# WATCHDOG.net
KiCad netlist of a schematic drawn in Altium Designer
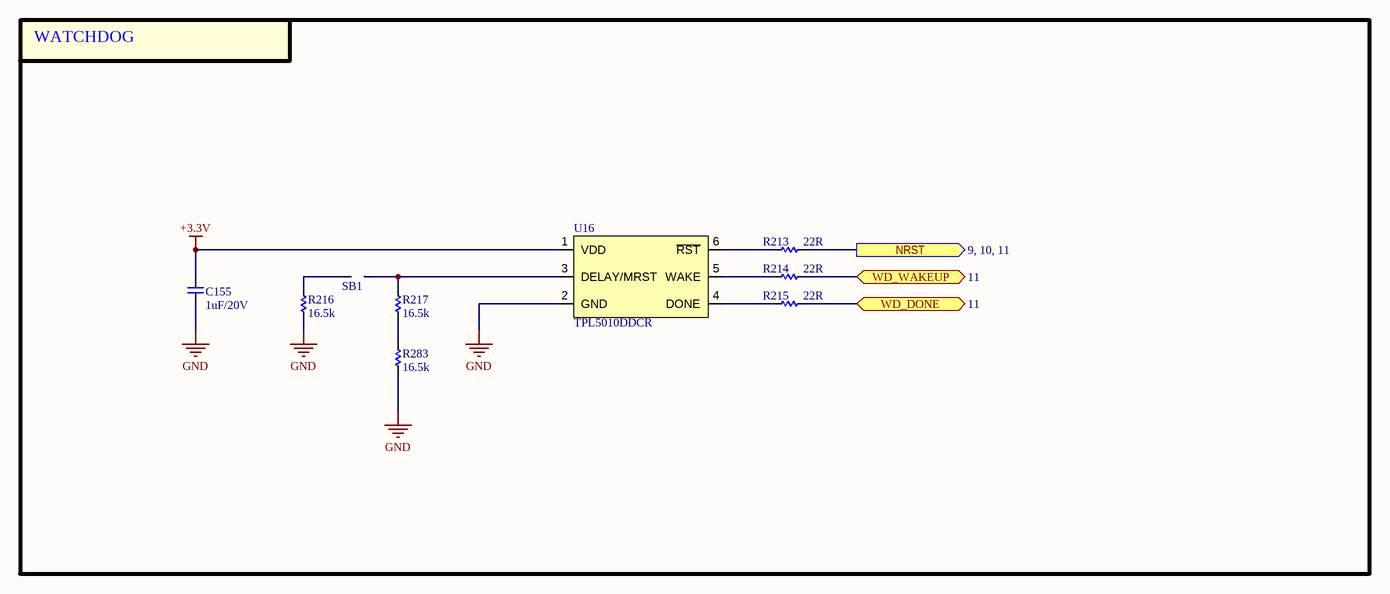
[diagram p0: WATCHDOG.SchDoc]

(export (version "E")
  (design (tool "Eeschema 10.0.6"))
  (components
    (comp (ref "C155")
      (value "1uF/20V")
      (footprint "CAP_C_1005X50_L")
      (description "CAP CHIP")
      (libsource (lib "IFBschelib") (part "_CAP_C_2"))
    )
    (comp (ref "R213")
      (value "22R")
      (footprint "RES_C_1005x30_L")
      (description "RES")
      (libsource (lib "LABLIB") (part "_RES_B_2"))
    )
    (comp (ref "R214")
      (value "22R")
      (footprint "RES_C_1005x30_L")
      (description "RES")
      (libsource (lib "LABLIB") (part "_RES_B_2"))
    )
    (comp (ref "R215")
      (value "22R")
      (footprint "RES_C_1005x30_L")
      (description "RES")
      (libsource (lib "LABLIB") (part "_RES_B_2"))
    )
    (comp (ref "R216")
      (value "16.5k")
      (footprint "RES_C_1005x30_L")
      (description "RES")
      (libsource (lib "IFBschelib") (part "_RES_B_2"))
    )
    (comp (ref "R217")
      (value "16.5k")
      (footprint "RES_C_1005x30_L")
      (description "RES")
      (libsource (lib "IFBschelib") (part "_RES_B_2"))
    )
    (comp (ref "R283")
      (value "16.5k")
      (footprint "RES_C_1005x30_L")
      (description "RES")
      (libsource (lib "IFBschelib") (part "_RES_B_2"))
    )
    (comp (ref "SB1")
      (value "JUMPER")
      (footprint "JUMPER_1608")
      (libsource (lib "IFBschelib") (part "JUMPER"))
    )
    (comp (ref "U16")
      (value "TPL5010DDCR")
      (footprint "TPL5010DDCR")
      (description "OSC PROG TIMER TSOT23-6")
      (libsource (lib "IFBschelib") (part "TPL5010DDCR"))
    )
  )
  (nets
    (net (code "1") (name "+3.3V") (class "Default")
      (node (ref "C155") (pin "2") (pinfunction "2_2") (pintype "passive"))
      (node (ref "U16") (pin "1") (pinfunction "VDD_1") (pintype "passive"))
    )
    (net (code "2") (name "/NRST") (class "Default")
      (node (ref "R213") (pin "2") (pinfunction "2_2") (pintype "passive"))
    )
    (net (code "3") (name "/WD_DONE") (class "Default")
      (node (ref "R215") (pin "2") (pinfunction "2_2") (pintype "passive"))
    )
    (net (code "4") (name "/WD_WAKEUP") (class "Default")
      (node (ref "R214") (pin "2") (pinfunction "2_2") (pintype "passive"))
    )
    (net (code "5") (name "GND") (class "Default")
      (node (ref "C155") (pin "1") (pinfunction "1_1") (pintype "passive"))
      (node (ref "R216") (pin "2") (pinfunction "2_2") (pintype "passive"))
      (node (ref "R283") (pin "2") (pinfunction "2_2") (pintype "passive"))
      (node (ref "U16") (pin "2") (pinfunction "GND_2") (pintype "passive"))
    )
    (net (code "6") (name "Net-(R216-Pad1)") (class "Default")
      (node (ref "R216") (pin "1") (pinfunction "1_1") (pintype "passive"))
      (node (ref "SB1") (pin "1") (pinfunction "1_1") (pintype "passive"))
    )
    (net (code "7") (name "Net-(R217-Pad2)") (class "Default")
      (node (ref "R217") (pin "2") (pinfunction "2_2") (pintype "passive"))
      (node (ref "R283") (pin "1") (pinfunction "1_1") (pintype "passive"))
    )
    (net (code "8") (name "Net-(U16-DELAY{slash}MRST)") (class "Default")
      (node (ref "R217") (pin "1") (pinfunction "1_1") (pintype "passive"))
      (node (ref "SB1") (pin "2") (pinfunction "2_2") (pintype "passive"))
      (node (ref "U16") (pin "3") (pinfunction "DELAY/MRST_3") (pintype "passive"))
    )
    (net (code "9") (name "Net-(U16-DONE)") (class "Default")
      (node (ref "R215") (pin "1") (pinfunction "1_1") (pintype "passive"))
      (node (ref "U16") (pin "4") (pinfunction "DONE_4") (pintype "passive"))
    )
    (net (code "10") (name "Net-(U16-WAKE)") (class "Default")
      (node (ref "R214") (pin "1") (pinfunction "1_1") (pintype "passive"))
      (node (ref "U16") (pin "5") (pinfunction "WAKE_5") (pintype "passive"))
    )
    (net (code "11") (name "Net-(U16-~{RST})") (class "Default")
      (node (ref "R213") (pin "1") (pinfunction "1_1") (pintype "passive"))
      (node (ref "U16") (pin "6") (pinfunction "~{RST}_6") (pintype "passive"))
    )
  )
)
